# harmonicAnalyzer_r002.net
KiCad netlist of a schematic drawn in Altium Designer
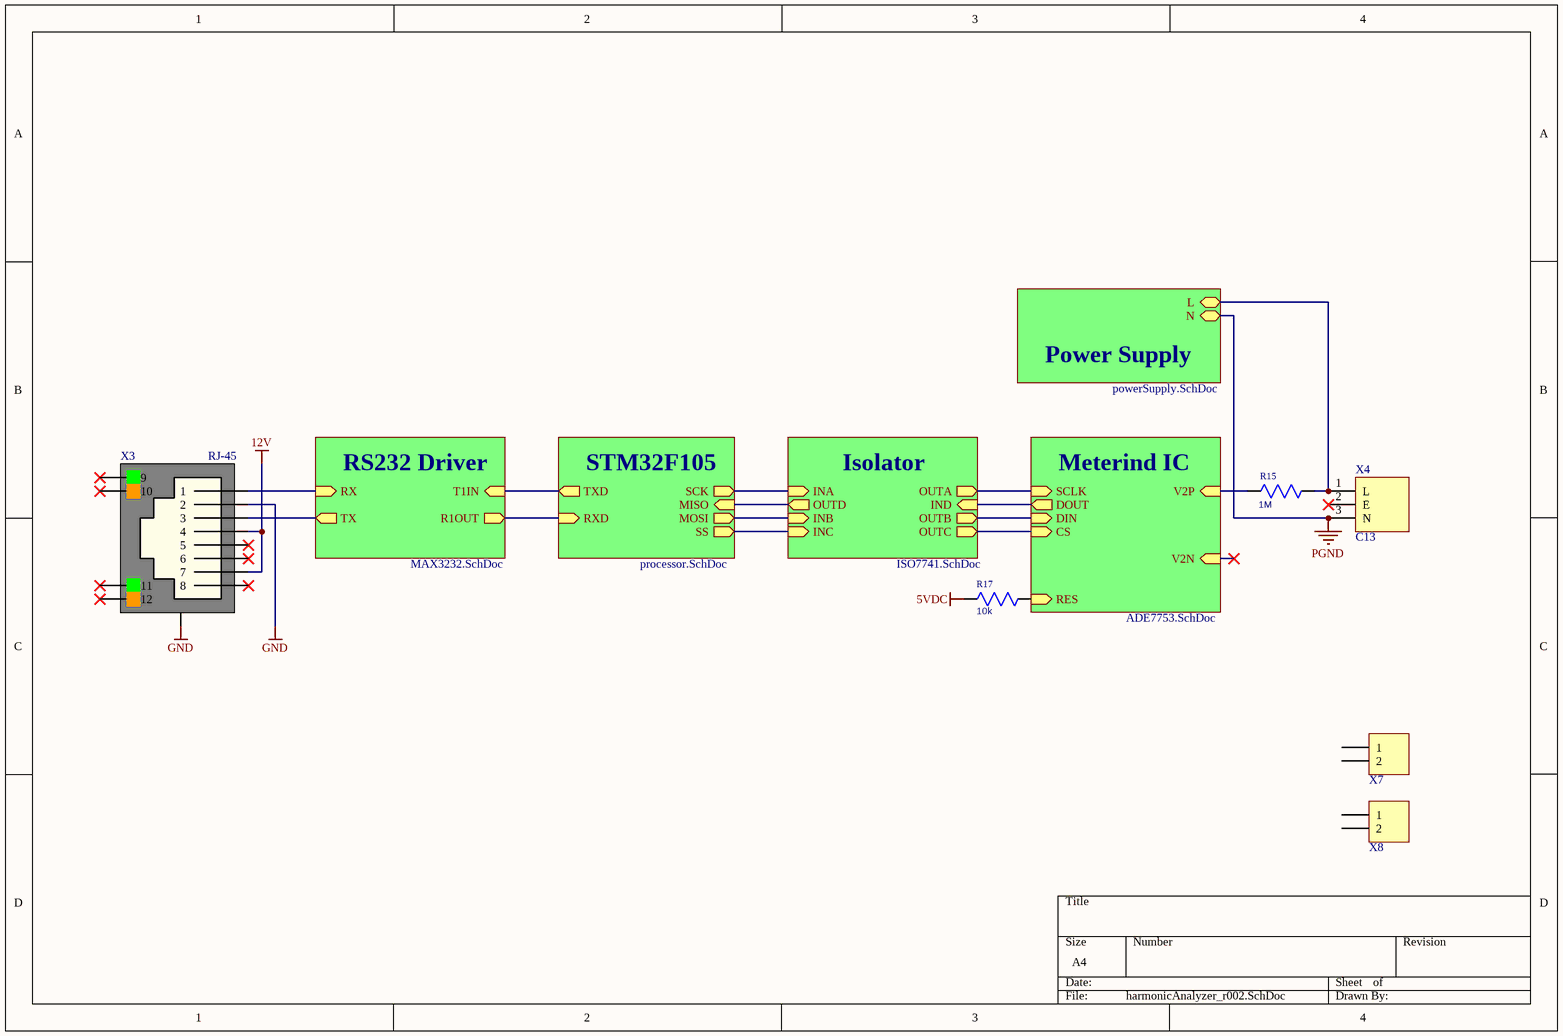
[diagram p0: harmonicAnalyzer_r002.SchDoc]

(export (version "E")
  (design (tool "Eeschema 10.0.6"))
  (components
    (comp (ref "R15")
      (value "1M")
      (footprint "R_0805")
      (description "Resistor")
      (libsource (lib "AX_Altium_v2.3") (part "R0805"))
    )
    (comp (ref "R17")
      (value "10k")
      (footprint "R_0603")
      (description "Resistor")
      (libsource (lib "AX_Altium_v2.3") (part "R0603"))
    )
    (comp (ref "X3")
      (value "RJ-45")
      (footprint "RJHSE-5E8X")
      (description "Jack Modular Connector")
      (libsource (lib "BublykIntegratedLibrary") (part "RJ-45"))
    )
    (comp (ref "X4")
      (value "C13")
      (footprint "C13_RA_TH")
      (libsource (lib "SmartOutletIntegratedLibrary") (part "C13"))
    )
    (comp (ref "X7")
      (value "PBS-2")
      (footprint "PBS-2-3D")
      (description "Header, 2-Pin")
      (fields (field (name "PUBLISHER") "Altium Limited"))
      (libsource (lib "AX_Altium_v2.3") (part "PBS-2"))
    )
    (comp (ref "X8")
      (value "PBS-2")
      (footprint "PBS-2-3D")
      (description "Header, 2-Pin")
      (fields (field (name "PUBLISHER") "Altium Limited"))
      (libsource (lib "AX_Altium_v2.3") (part "PBS-2"))
    )
  )
  (nets
    (net (code "2") (name "/L") (class "Default")
      (node (ref "R15") (pin "2") (pintype "passive"))
      (node (ref "X4") (pin "1") (pinfunction "L_1") (pintype "passive"))
    )
    (net (code "9") (name "/RES") (class "Default") (node (ref "R17") (pin "2") (pintype "passive")))
    (net (code "10") (name "/RX") (class "Default")
      (node (ref "X3") (pin "1") (pinfunction "1_1") (pintype "passive"))
    )
    (net (code "13") (name "/TX") (class "Default")
      (node (ref "X3") (pin "3") (pinfunction "3_3") (pintype "passive"))
    )
    (net (code "16") (name "/V2P") (class "Default") (node (ref "R15") (pin "1") (pintype "passive")))
    (net (code "17") (name "5VDC") (class "Default") (node (ref "R17") (pin "1") (pintype "passive")))
    (net (code "18") (name "12V") (class "Default")
      (node (ref "X3") (pin "4") (pinfunction "4_4") (pintype "passive"))
      (node (ref "X3") (pin "7") (pinfunction "7_7") (pintype "passive"))
    )
    (net (code "19") (name "GND") (class "Default")
      (node (ref "X3") (pin "13") (pinfunction "13_13") (pintype "passive"))
      (node (ref "X3") (pin "2") (pinfunction "2_2") (pintype "passive"))
    )
    (net (code "20") (name "PGND") (class "Default")
      (node (ref "X4") (pin "3") (pinfunction "N_3") (pintype "passive"))
    )
    (net (code "21") (name "unconnected-(X3-Pad5)") (class "Default")
      (node (ref "X3") (pin "5") (pinfunction "5_5") (pintype "passive+no_connect"))
    )
    (net (code "22") (name "unconnected-(X3-Pad6)") (class "Default")
      (node (ref "X3") (pin "6") (pinfunction "6_6") (pintype "passive+no_connect"))
    )
    (net (code "23") (name "unconnected-(X3-Pad8)") (class "Default")
      (node (ref "X3") (pin "8") (pinfunction "8_8") (pintype "passive+no_connect"))
    )
    (net (code "24") (name "unconnected-(X3-Pad9)") (class "Default")
      (node (ref "X3") (pin "9") (pinfunction "9_9") (pintype "passive+no_connect"))
    )
    (net (code "25") (name "unconnected-(X3-Pad10)") (class "Default")
      (node (ref "X3") (pin "10") (pinfunction "10_10") (pintype "passive+no_connect"))
    )
    (net (code "26") (name "unconnected-(X3-Pad11)") (class "Default")
      (node (ref "X3") (pin "11") (pinfunction "11_11") (pintype "passive+no_connect"))
    )
    (net (code "27") (name "unconnected-(X3-Pad12)") (class "Default")
      (node (ref "X3") (pin "12") (pinfunction "12_12") (pintype "passive+no_connect"))
    )
    (net (code "28") (name "unconnected-(X4-E-Pad2)") (class "Default")
      (node (ref "X4") (pin "2") (pinfunction "E_2") (pintype "passive+no_connect"))
    )
    (net (code "29") (name "unconnected-(X7-Pad1)") (class "Default")
      (node (ref "X7") (pin "1") (pinfunction "1_1") (pintype "passive"))
    )
    (net (code "30") (name "unconnected-(X7-Pad2)") (class "Default")
      (node (ref "X7") (pin "2") (pinfunction "2_2") (pintype "passive"))
    )
    (net (code "31") (name "unconnected-(X8-Pad1)") (class "Default")
      (node (ref "X8") (pin "1") (pinfunction "1_1") (pintype "passive"))
    )
    (net (code "32") (name "unconnected-(X8-Pad2)") (class "Default")
      (node (ref "X8") (pin "2") (pinfunction "2_2") (pintype "passive"))
    )
  )
)
